# RGB_Display.net
KiCad netlist of a schematic drawn in Altium Designer
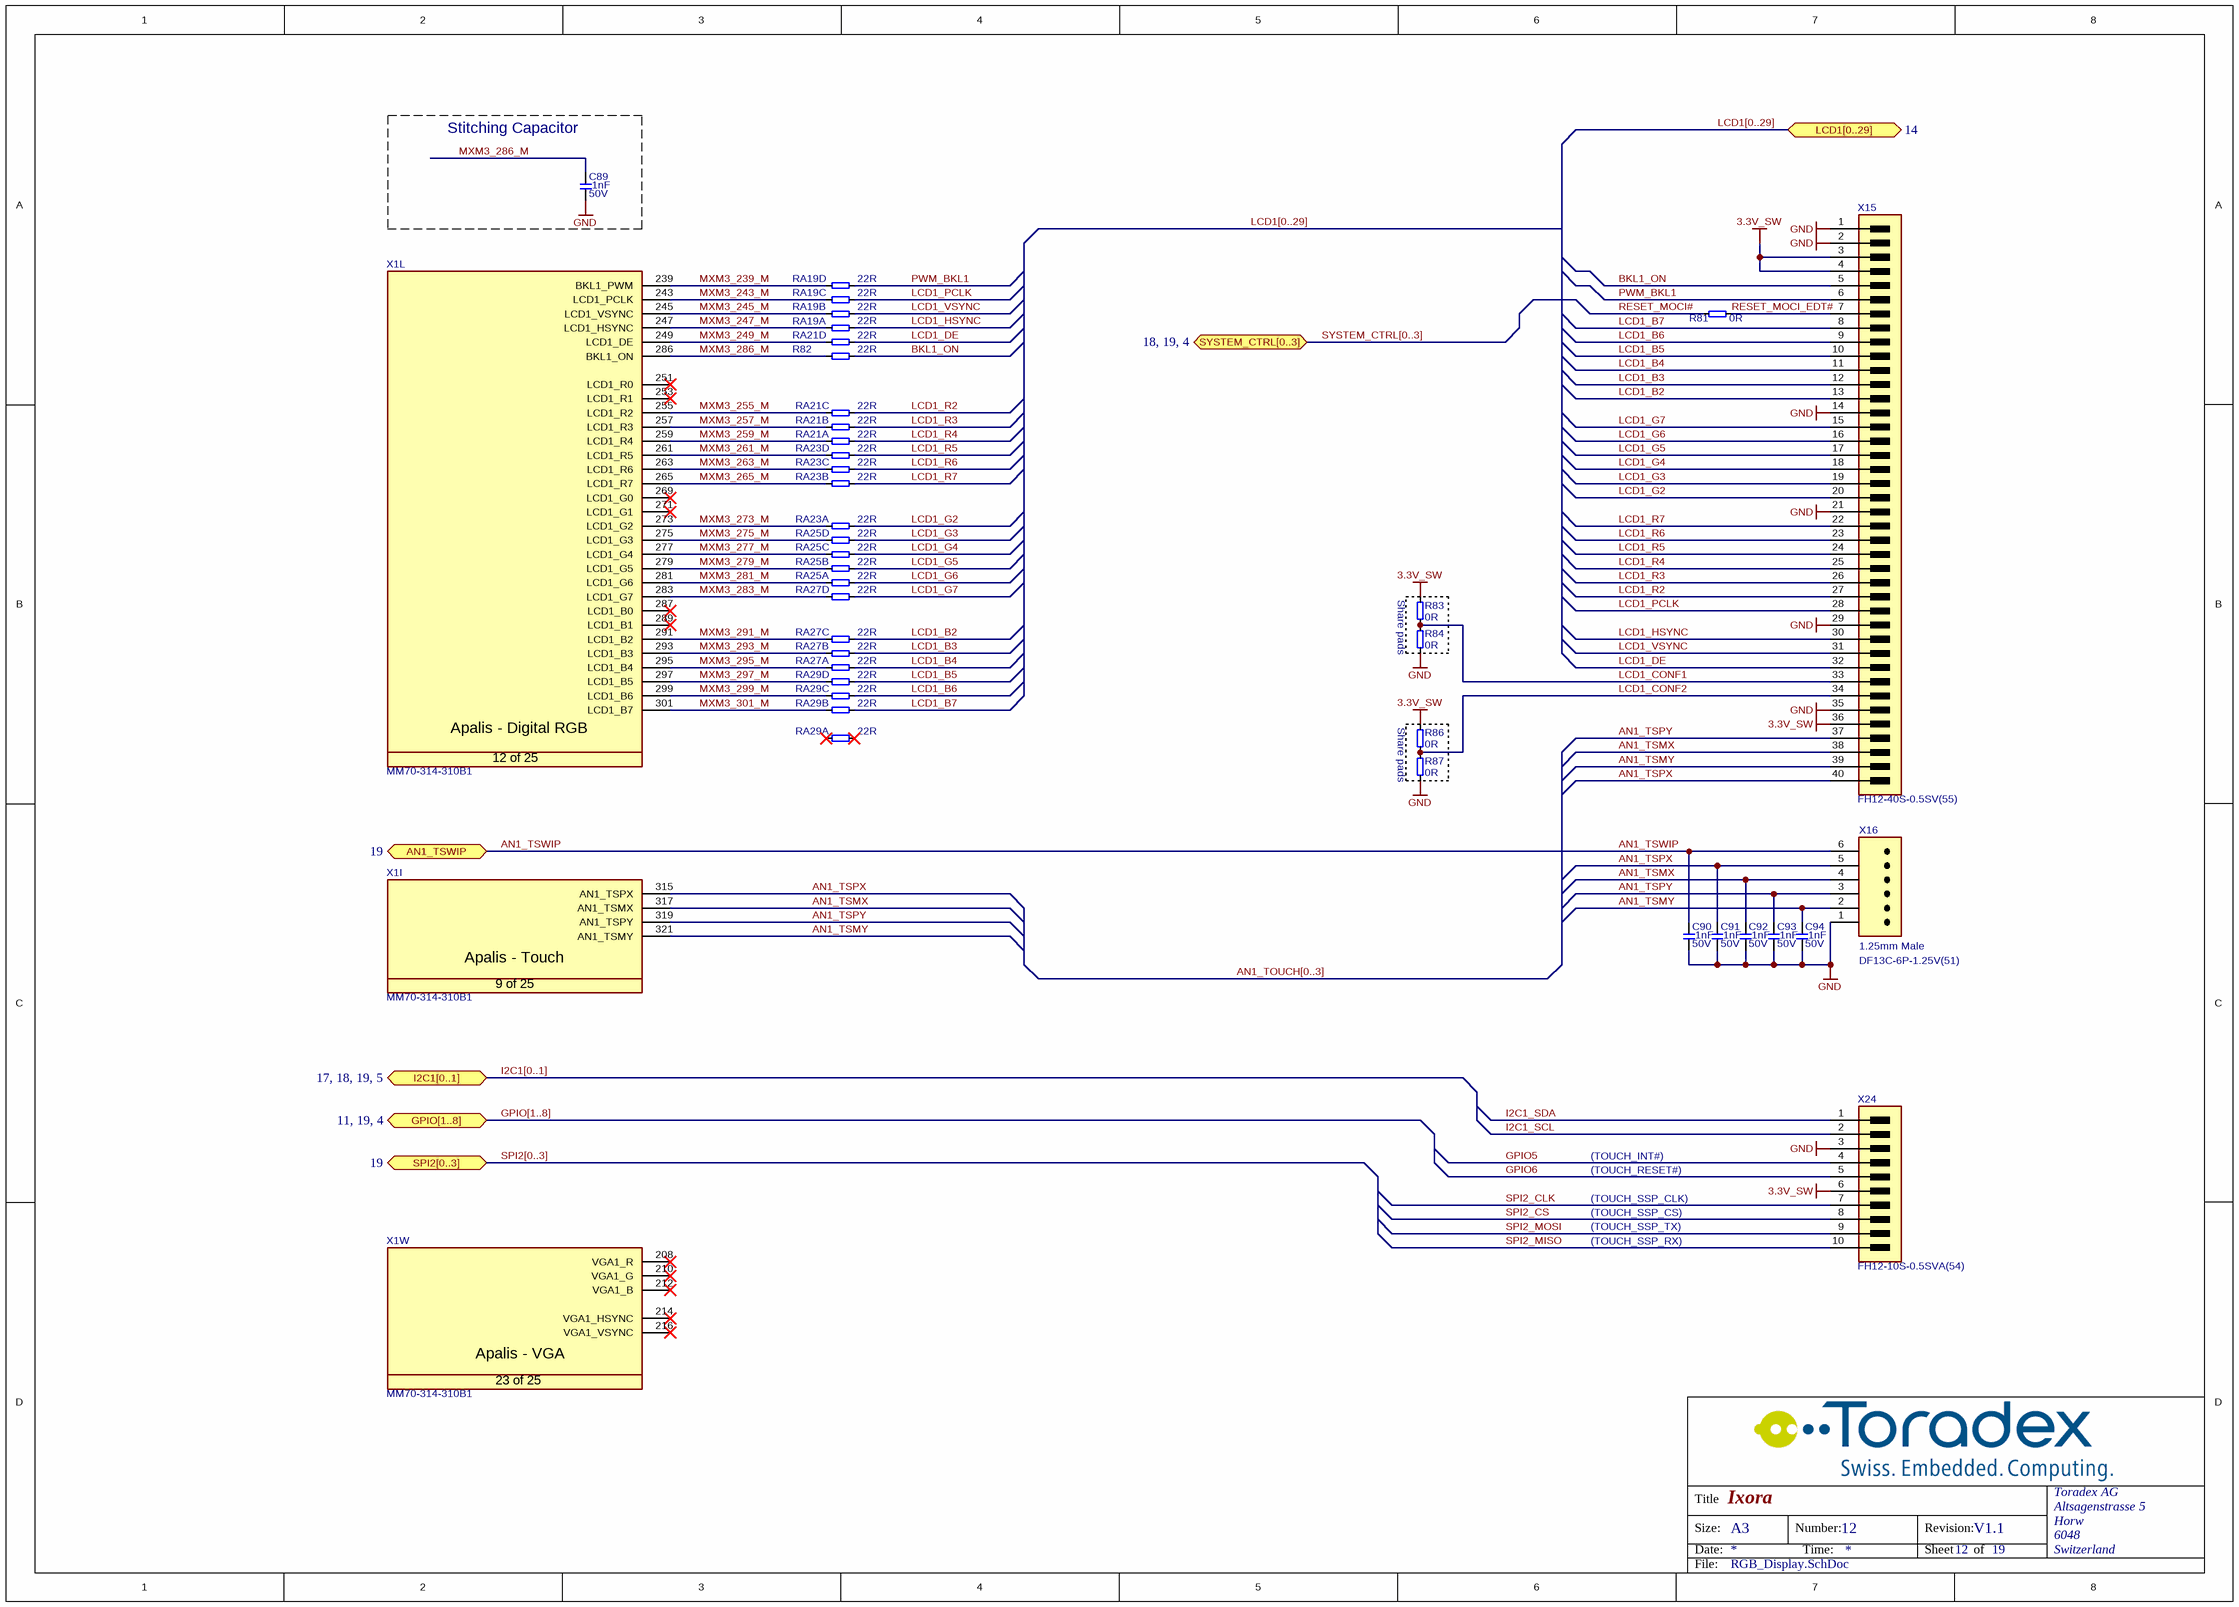
[diagram p0: RGB_Display.SchDoc]

(export (version "E")
  (design (tool "Eeschema 10.0.6"))
  (components
    (comp (ref "C89")
      (value "1nF")
      (footprint "CAPC1005X60N")
      (description "Capacitor Ceramic X7R 1nF 50V 10% 0402")
      (fields (field (name "TOLERANCE") "10%") (field (name "RATING") "50V"))
      (libsource (lib "Ixora") (part "C-X7R-1nF-50V-10%-0402"))
    )
    (comp (ref "C90")
      (value "1nF")
      (footprint "CAPC1005X60N")
      (description "Capacitor Ceramic X7R 1nF 50V 10% 0402")
      (fields (field (name "TOLERANCE") "10%") (field (name "RATING") "50V"))
      (libsource (lib "Ixora") (part "C-X7R-1nF-50V-10%-0402"))
    )
    (comp (ref "C91")
      (value "1nF")
      (footprint "CAPC1005X60N")
      (description "Capacitor Ceramic X7R 1nF 50V 10% 0402")
      (fields (field (name "TOLERANCE") "10%") (field (name "RATING") "50V"))
      (libsource (lib "Ixora") (part "C-X7R-1nF-50V-10%-0402"))
    )
    (comp (ref "C92")
      (value "1nF")
      (footprint "CAPC1005X60N")
      (description "Capacitor Ceramic X7R 1nF 50V 10% 0402")
      (fields (field (name "TOLERANCE") "10%") (field (name "RATING") "50V"))
      (libsource (lib "Ixora") (part "C-X7R-1nF-50V-10%-0402"))
    )
    (comp (ref "C93")
      (value "1nF")
      (footprint "CAPC1005X60N")
      (description "Capacitor Ceramic X7R 1nF 50V 10% 0402")
      (fields (field (name "TOLERANCE") "10%") (field (name "RATING") "50V"))
      (libsource (lib "Ixora") (part "C-X7R-1nF-50V-10%-0402"))
    )
    (comp (ref "C94")
      (value "1nF")
      (footprint "CAPC1005X60N")
      (description "Capacitor Ceramic X7R 1nF 50V 10% 0402")
      (fields (field (name "TOLERANCE") "10%") (field (name "RATING") "50V"))
      (libsource (lib "Ixora") (part "C-X7R-1nF-50V-10%-0402"))
    )
    (comp (ref "R81")
      (value "0R")
      (footprint "RESC1005X40N")
      (description "Resistor 0 ohm 63mW 1% 0402")
      (fields (field (name "TOLERANCE") "1%"))
      (libsource (lib "Ixora") (part "R-0R-63mW-1%-0402"))
    )
    (comp (ref "R82")
      (value "22R")
      (footprint "RESC1005X40N")
      (description "Resistor 22 ohm 63mW 5% 0402")
      (fields (field (name "TOLERANCE") "5%"))
      (libsource (lib "Ixora") (part "R-22R-63mW-5%-0402"))
    )
    (comp (ref "R83")
      (value "0R")
      (footprint "T_RESC0603X30N")
      (description "Resistor 0 ohm 63mW 1% 0603")
      (fields (field (name "TOLERANCE") "1%"))
      (libsource (lib "Ixora") (part "R-0R-63mW-1%-0603"))
    )
    (comp (ref "R84")
      (value "0R")
      (footprint "T_RESC0603X30N")
      (description "Resistor 0 ohm 63mW 1% 0603")
      (fields (field (name "TOLERANCE") "1%"))
      (libsource (lib "Ixora") (part "R-0R-63mW-1%-0603"))
    )
    (comp (ref "R86")
      (value "0R")
      (footprint "T_RESC0603X30N")
      (description "Resistor 0 ohm 63mW 1% 0603")
      (fields (field (name "TOLERANCE") "1%"))
      (libsource (lib "Ixora") (part "R-0R-63mW-1%-0603"))
    )
    (comp (ref "R87")
      (value "0R")
      (footprint "T_RESC0603X30N")
      (description "Resistor 0 ohm 63mW 1% 0603")
      (fields (field (name "TOLERANCE") "1%"))
      (libsource (lib "Ixora") (part "R-0R-63mW-1%-0603"))
    )
    (comp (ref "RA19")
      (value "22R")
      (footprint "T_Resistor_Array_X4")
      (description "Resistor Array 22 R 63mW 5% 1206")
      (fields (field (name "TOLERANCE") "5%"))
      (libsource (lib "Ixora") (part "RA-22R-63mW-5%-1206-div"))
    )
    (comp (ref "RA21")
      (value "22R")
      (footprint "T_Resistor_Array_X4")
      (description "Resistor Array 22 R 63mW 5% 1206")
      (fields (field (name "TOLERANCE") "5%"))
      (libsource (lib "Ixora") (part "RA-22R-63mW-5%-1206-div"))
    )
    (comp (ref "RA23")
      (value "22R")
      (footprint "T_Resistor_Array_X4")
      (description "Resistor Array 22 R 63mW 5% 1206")
      (fields (field (name "TOLERANCE") "5%"))
      (libsource (lib "Ixora") (part "RA-22R-63mW-5%-1206-div"))
    )
    (comp (ref "RA25")
      (value "22R")
      (footprint "T_Resistor_Array_X4")
      (description "Resistor Array 22 R 63mW 5% 1206")
      (fields (field (name "TOLERANCE") "5%"))
      (libsource (lib "Ixora") (part "RA-22R-63mW-5%-1206-div"))
    )
    (comp (ref "RA27")
      (value "22R")
      (footprint "T_Resistor_Array_X4")
      (description "Resistor Array 22 R 63mW 5% 1206")
      (fields (field (name "TOLERANCE") "5%"))
      (libsource (lib "Ixora") (part "RA-22R-63mW-5%-1206-div"))
    )
    (comp (ref "RA29")
      (value "22R")
      (footprint "T_Resistor_Array_X4")
      (description "Resistor Array 22 R 63mW 5% 1206")
      (fields (field (name "TOLERANCE") "5%"))
      (libsource (lib "Ixora") (part "RA-22R-63mW-5%-1206-div"))
    )
    (comp (ref "X1")
      (value "CON-JAE-MM70-314-310B1-314-0.5mm")
      (footprint "T_JAE_MM70-314-310B1")
      (description "MXM3 Connector")
      (fields (field (name "MANUFACTURER PART NO.") "MM70-314-310B1"))
      (libsource (lib "Ixora") (part "CON-JAE-MM70-314-310B1-314-0.5mm"))
    )
    (comp (ref "X15")
      (value "FH12-40S-0.5SV(55)")
      (footprint "T_Hirose_FH12-40S-0.5SV(55)")
      (description "0.50mm Pitch FFC/FPC Vertical RGB connector")
      (fields (field (name "MANUFACTURER PART NO.") "FH12-40S-0.5SV(55)"))
      (libsource (lib "Ixora") (part "CON-Hirose-FH12-40S-0.5SV(55)-0.5mm"))
    )
    (comp (ref "X16")
      (value "DF13C-6P-1.25V(51)")
      (footprint "T_HIROSE_DF13C-6P-1.25V(51)")
      (description "Touch Connector")
      (fields (field (name "MANUFACTURER PART NO.") "DF13C-6P-1.25V(51)"))
      (libsource (lib "Ixora") (part "CON-Hirose-DF13C-6P-1.25V(51)-1x6-1.25mm"))
    )
    (comp (ref "X24")
      (value "FH12-10S-0.5SVA(54)")
      (footprint "T_Hirose_FH12-10S-0.5SVA(54)")
      (description "FFC/FPC, 1 Sided Contact, 0.50mm Pitch, 10 pins")
      (fields (field (name "MANUFACTURER PART NO.") "FH12-10S-0.5SVA(54)"))
      (libsource (lib "Ixora") (part "CON-Hirose-FH12-10S-0.5SVA(54)-0.5mm"))
    )
  )
  (nets
    (net (code "52") (name "/AN1_TSMX") (class "Default")
      (node (ref "C92") (pin "2") (pinfunction "2_2") (pintype "passive"))
      (node (ref "X1") (pin "317") (pinfunction "AN1_TSMX_317") (pintype "passive"))
      (node (ref "X15") (pin "38") (pinfunction "XR_38") (pintype "passive"))
      (node (ref "X16") (pin "4") (pinfunction "TSMX_4") (pintype "passive"))
    )
    (net (code "53") (name "/AN1_TSMY") (class "Default")
      (node (ref "C94") (pin "2") (pinfunction "2_2") (pintype "passive"))
      (node (ref "X1") (pin "321") (pinfunction "AN1_TSMY_321") (pintype "passive"))
      (node (ref "X15") (pin "39") (pinfunction "YD_39") (pintype "passive"))
      (node (ref "X16") (pin "2") (pinfunction "TSMY_2") (pintype "passive"))
    )
    (net (code "54") (name "/AN1_TSPX") (class "Default")
      (node (ref "C91") (pin "2") (pinfunction "2_2") (pintype "passive"))
      (node (ref "X1") (pin "315") (pinfunction "AN1_TSPX_315") (pintype "passive"))
      (node (ref "X15") (pin "40") (pinfunction "XL_40") (pintype "passive"))
      (node (ref "X16") (pin "5") (pinfunction "TSPX_5") (pintype "passive"))
    )
    (net (code "55") (name "/AN1_TSPY") (class "Default")
      (node (ref "C93") (pin "2") (pinfunction "2_2") (pintype "passive"))
      (node (ref "X1") (pin "319") (pinfunction "AN1_TSPY_319") (pintype "passive"))
      (node (ref "X15") (pin "37") (pinfunction "YU_37") (pintype "passive"))
      (node (ref "X16") (pin "3") (pinfunction "TSPY_3") (pintype "passive"))
    )
    (net (code "56") (name "/AN1_TSWIP") (class "Default")
      (node (ref "C90") (pin "2") (pinfunction "2_2") (pintype "passive"))
      (node (ref "X16") (pin "6") (pinfunction "WIPER_6") (pintype "passive"))
    )
    (net (code "57") (name "/BKL1_ON") (class "Default")
      (node (ref "R82") (pin "2") (pinfunction "2_2") (pintype "passive"))
      (node (ref "X15") (pin "5") (pinfunction "PWCTRL_5") (pintype "passive"))
    )
    (net (code "58") (name "/GPIO5") (class "Default")
      (node (ref "X24") (pin "4") (pinfunction "GND_4") (pintype "passive"))
    )
    (net (code "59") (name "/GPIO6") (class "Default")
      (node (ref "X24") (pin "5") (pinfunction "TMDS_DATA0_P_5") (pintype "passive"))
    )
    (net (code "62") (name "/I2C1_SCL") (class "Default")
      (node (ref "X24") (pin "2") (pinfunction "TMDS_CLK_P_2") (pintype "passive"))
    )
    (net (code "63") (name "/I2C1_SDA") (class "Default")
      (node (ref "X24") (pin "1") (pinfunction "GND_1") (pintype "passive"))
    )
    (net (code "65") (name "/LCD1_B2") (class "Default")
      (node (ref "RA27") (pin "7") (pinfunction "7_7") (pintype "passive"))
      (node (ref "X15") (pin "13") (pinfunction "B0_13") (pintype "passive"))
    )
    (net (code "66") (name "/LCD1_B3") (class "Default")
      (node (ref "RA27") (pin "6") (pinfunction "6_6") (pintype "passive"))
      (node (ref "X15") (pin "12") (pinfunction "B1_12") (pintype "passive"))
    )
    (net (code "67") (name "/LCD1_B4") (class "Default")
      (node (ref "RA27") (pin "5") (pinfunction "5_5") (pintype "passive"))
      (node (ref "X15") (pin "11") (pinfunction "B2_11") (pintype "passive"))
    )
    (net (code "68") (name "/LCD1_B5") (class "Default")
      (node (ref "RA29") (pin "8") (pinfunction "8_8") (pintype "passive"))
      (node (ref "X15") (pin "10") (pinfunction "B3_10") (pintype "passive"))
    )
    (net (code "69") (name "/LCD1_B6") (class "Default")
      (node (ref "RA29") (pin "7") (pinfunction "7_7") (pintype "passive"))
      (node (ref "X15") (pin "9") (pinfunction "B4_9") (pintype "passive"))
    )
    (net (code "70") (name "/LCD1_B7") (class "Default")
      (node (ref "RA29") (pin "6") (pinfunction "6_6") (pintype "passive"))
      (node (ref "X15") (pin "8") (pinfunction "B5_8") (pintype "passive"))
    )
    (net (code "71") (name "/LCD1_CONF1") (class "Default")
      (node (ref "R83") (pin "2") (pinfunction "2_2") (pintype "passive"))
      (node (ref "R84") (pin "1") (pinfunction "1_1") (pintype "passive"))
      (node (ref "X15") (pin "33") (pinfunction "NC_33") (pintype "passive"))
    )
    (net (code "72") (name "/LCD1_CONF2") (class "Default")
      (node (ref "R86") (pin "2") (pinfunction "2_2") (pintype "passive"))
      (node (ref "R87") (pin "2") (pinfunction "2_2") (pintype "passive"))
      (node (ref "X15") (pin "34") (pinfunction "SHUT_34") (pintype "passive"))
    )
    (net (code "73") (name "/LCD1_DE") (class "Default")
      (node (ref "RA21") (pin "8") (pinfunction "8_8") (pintype "passive"))
      (node (ref "X15") (pin "32") (pinfunction "ENB_32") (pintype "passive"))
    )
    (net (code "74") (name "/LCD1_G2") (class "Default")
      (node (ref "RA23") (pin "5") (pinfunction "5_5") (pintype "passive"))
      (node (ref "X15") (pin "20") (pinfunction "G0_20") (pintype "passive"))
    )
    (net (code "75") (name "/LCD1_G3") (class "Default")
      (node (ref "RA25") (pin "8") (pinfunction "8_8") (pintype "passive"))
      (node (ref "X15") (pin "19") (pinfunction "G1_19") (pintype "passive"))
    )
    (net (code "76") (name "/LCD1_G4") (class "Default")
      (node (ref "RA25") (pin "7") (pinfunction "7_7") (pintype "passive"))
      (node (ref "X15") (pin "18") (pinfunction "G2_18") (pintype "passive"))
    )
    (net (code "77") (name "/LCD1_G5") (class "Default")
      (node (ref "RA25") (pin "6") (pinfunction "6_6") (pintype "passive"))
      (node (ref "X15") (pin "17") (pinfunction "G3_17") (pintype "passive"))
    )
    (net (code "78") (name "/LCD1_G6") (class "Default")
      (node (ref "RA25") (pin "5") (pinfunction "5_5") (pintype "passive"))
      (node (ref "X15") (pin "16") (pinfunction "G4_16") (pintype "passive"))
    )
    (net (code "79") (name "/LCD1_G7") (class "Default")
      (node (ref "RA27") (pin "8") (pinfunction "8_8") (pintype "passive"))
      (node (ref "X15") (pin "15") (pinfunction "G5_15") (pintype "passive"))
    )
    (net (code "80") (name "/LCD1_HSYNC") (class "Default")
      (node (ref "RA19") (pin "5") (pinfunction "5_5") (pintype "passive"))
      (node (ref "X15") (pin "30") (pinfunction "HSYNC_30") (pintype "passive"))
    )
    (net (code "81") (name "/LCD1_PCLK") (class "Default")
      (node (ref "RA19") (pin "7") (pinfunction "7_7") (pintype "passive"))
      (node (ref "X15") (pin "28") (pinfunction "DCLK_28") (pintype "passive"))
    )
    (net (code "82") (name "/LCD1_R2") (class "Default")
      (node (ref "RA21") (pin "7") (pinfunction "7_7") (pintype "passive"))
      (node (ref "X15") (pin "27") (pinfunction "R0_27") (pintype "passive"))
    )
    (net (code "83") (name "/LCD1_R3") (class "Default")
      (node (ref "RA21") (pin "6") (pinfunction "6_6") (pintype "passive"))
      (node (ref "X15") (pin "26") (pinfunction "R1_26") (pintype "passive"))
    )
    (net (code "84") (name "/LCD1_R4") (class "Default")
      (node (ref "RA21") (pin "5") (pinfunction "5_5") (pintype "passive"))
      (node (ref "X15") (pin "25") (pinfunction "R2_25") (pintype "passive"))
    )
    (net (code "85") (name "/LCD1_R5") (class "Default")
      (node (ref "RA23") (pin "8") (pinfunction "8_8") (pintype "passive"))
      (node (ref "X15") (pin "24") (pinfunction "R3_24") (pintype "passive"))
    )
    (net (code "86") (name "/LCD1_R6") (class "Default")
      (node (ref "RA23") (pin "7") (pinfunction "7_7") (pintype "passive"))
      (node (ref "X15") (pin "23") (pinfunction "R4_23") (pintype "passive"))
    )
    (net (code "87") (name "/LCD1_R7") (class "Default")
      (node (ref "RA23") (pin "6") (pinfunction "6_6") (pintype "passive"))
      (node (ref "X15") (pin "22") (pinfunction "R5_22") (pintype "passive"))
    )
    (net (code "88") (name "/LCD1_VSYNC") (class "Default")
      (node (ref "RA19") (pin "6") (pinfunction "6_6") (pintype "passive"))
      (node (ref "X15") (pin "31") (pinfunction "VSYNC_31") (pintype "passive"))
    )
    (net (code "89") (name "/MXM3_239_M") (class "Default")
      (node (ref "RA19") (pin "4") (pinfunction "4_4") (pintype "passive"))
      (node (ref "X1") (pin "239") (pinfunction "BKL1_PWM_239") (pintype "passive"))
    )
    (net (code "90") (name "/MXM3_243_M") (class "Default")
      (node (ref "RA19") (pin "3") (pinfunction "3_3") (pintype "passive"))
      (node (ref "X1") (pin "243") (pinfunction "LCD1_PCLK_243") (pintype "passive"))
    )
    (net (code "91") (name "/MXM3_245_M") (class "Default")
      (node (ref "RA19") (pin "2") (pinfunction "2_2") (pintype "passive"))
      (node (ref "X1") (pin "245") (pinfunction "LCD1_VSYNC_245") (pintype "passive"))
    )
    (net (code "92") (name "/MXM3_247_M") (class "Default")
      (node (ref "RA19") (pin "1") (pinfunction "1_1") (pintype "passive"))
      (node (ref "X1") (pin "247") (pinfunction "LCD1_HSYNC_247") (pintype "passive"))
    )
    (net (code "93") (name "/MXM3_249_M") (class "Default")
      (node (ref "RA21") (pin "4") (pinfunction "4_4") (pintype "passive"))
      (node (ref "X1") (pin "249") (pinfunction "LCD1_DE_249") (pintype "passive"))
    )
    (net (code "94") (name "/MXM3_255_M") (class "Default")
      (node (ref "RA21") (pin "3") (pinfunction "3_3") (pintype "passive"))
      (node (ref "X1") (pin "255") (pinfunction "LCD1_R2_255") (pintype "passive"))
    )
    (net (code "95") (name "/MXM3_257_M") (class "Default")
      (node (ref "RA21") (pin "2") (pinfunction "2_2") (pintype "passive"))
      (node (ref "X1") (pin "257") (pinfunction "LCD1_R3_257") (pintype "passive"))
    )
    (net (code "96") (name "/MXM3_259_M") (class "Default")
      (node (ref "RA21") (pin "1") (pinfunction "1_1") (pintype "passive"))
      (node (ref "X1") (pin "259") (pinfunction "LCD1_R4_259") (pintype "passive"))
    )
    (net (code "97") (name "/MXM3_261_M") (class "Default")
      (node (ref "RA23") (pin "4") (pinfunction "4_4") (pintype "passive"))
      (node (ref "X1") (pin "261") (pinfunction "LCD1_R5_261") (pintype "passive"))
    )
    (net (code "98") (name "/MXM3_263_M") (class "Default")
      (node (ref "RA23") (pin "3") (pinfunction "3_3") (pintype "passive"))
      (node (ref "X1") (pin "263") (pinfunction "LCD1_R6_263") (pintype "passive"))
    )
    (net (code "99") (name "/MXM3_265_M") (class "Default")
      (node (ref "RA23") (pin "2") (pinfunction "2_2") (pintype "passive"))
      (node (ref "X1") (pin "265") (pinfunction "LCD1_R7_265") (pintype "passive"))
    )
    (net (code "100") (name "/MXM3_273_M") (class "Default")
      (node (ref "RA23") (pin "1") (pinfunction "1_1") (pintype "passive"))
      (node (ref "X1") (pin "273") (pinfunction "LCD1_G2_273") (pintype "passive"))
    )
    (net (code "101") (name "/MXM3_275_M") (class "Default")
      (node (ref "RA25") (pin "4") (pinfunction "4_4") (pintype "passive"))
      (node (ref "X1") (pin "275") (pinfunction "LCD1_G3_275") (pintype "passive"))
    )
    (net (code "102") (name "/MXM3_277_M") (class "Default")
      (node (ref "RA25") (pin "3") (pinfunction "3_3") (pintype "passive"))
      (node (ref "X1") (pin "277") (pinfunction "LCD1_G4_277") (pintype "passive"))
    )
    (net (code "103") (name "/MXM3_279_M") (class "Default")
      (node (ref "RA25") (pin "2") (pinfunction "2_2") (pintype "passive"))
      (node (ref "X1") (pin "279") (pinfunction "LCD1_G5_279") (pintype "passive"))
    )
    (net (code "104") (name "/MXM3_281_M") (class "Default")
      (node (ref "RA25") (pin "1") (pinfunction "1_1") (pintype "passive"))
      (node (ref "X1") (pin "281") (pinfunction "LCD1_G6_281") (pintype "passive"))
    )
    (net (code "105") (name "/MXM3_283_M") (class "Default")
      (node (ref "RA27") (pin "4") (pinfunction "4_4") (pintype "passive"))
      (node (ref "X1") (pin "283") (pinfunction "LCD1_G7_283") (pintype "passive"))
    )
    (net (code "106") (name "/MXM3_286_M") (class "Default")
      (node (ref "C89") (pin "2") (pinfunction "2_2") (pintype "passive"))
      (node (ref "R82") (pin "1") (pinfunction "1_1") (pintype "passive"))
      (node (ref "X1") (pin "286") (pinfunction "BKL1_ON_286") (pintype "passive"))
    )
    (net (code "107") (name "/MXM3_291_M") (class "Default")
      (node (ref "RA27") (pin "3") (pinfunction "3_3") (pintype "passive"))
      (node (ref "X1") (pin "291") (pinfunction "LCD1_B2_291") (pintype "passive"))
    )
    (net (code "108") (name "/MXM3_293_M") (class "Default")
      (node (ref "RA27") (pin "2") (pinfunction "2_2") (pintype "passive"))
      (node (ref "X1") (pin "293") (pinfunction "LCD1_B3_293") (pintype "passive"))
    )
    (net (code "109") (name "/MXM3_295_M") (class "Default")
      (node (ref "RA27") (pin "1") (pinfunction "1_1") (pintype "passive"))
      (node (ref "X1") (pin "295") (pinfunction "LCD1_B4_295") (pintype "passive"))
    )
    (net (code "110") (name "/MXM3_297_M") (class "Default")
      (node (ref "RA29") (pin "4") (pinfunction "4_4") (pintype "passive"))
      (node (ref "X1") (pin "297") (pinfunction "LCD1_B5_297") (pintype "passive"))
    )
    (net (code "111") (name "/MXM3_299_M") (class "Default")
      (node (ref "RA29") (pin "3") (pinfunction "3_3") (pintype "passive"))
      (node (ref "X1") (pin "299") (pinfunction "LCD1_B6_299") (pintype "passive"))
    )
    (net (code "112") (name "/MXM3_301_M") (class "Default")
      (node (ref "RA29") (pin "2") (pinfunction "2_2") (pintype "passive"))
      (node (ref "X1") (pin "301") (pinfunction "LCD1_B7_301") (pintype "passive"))
    )
    (net (code "113") (name "/PWM_BKL1") (class "Default")
      (node (ref "RA19") (pin "8") (pinfunction "8_8") (pintype "passive"))
      (node (ref "X15") (pin "6") (pinfunction "LEDCTRL_6") (pintype "passive"))
    )
    (net (code "114") (name "/RESET_MOCI#") (class "Default")
      (node (ref "R81") (pin "1") (pinfunction "1_1") (pintype "passive"))
    )
    (net (code "115") (name "/RESET_MOCI_EDT#") (class "Default")
      (node (ref "R81") (pin "2") (pinfunction "2_2") (pintype "passive"))
      (node (ref "X15") (pin "7") (pinfunction "RESET#_7") (pintype "passive"))
    )
    (net (code "117") (name "/SPI2_CLK") (class "Default")
      (node (ref "X24") (pin "7") (pinfunction "GND_7") (pintype "passive"))
    )
    (net (code "118") (name "/SPI2_CS") (class "Default")
      (node (ref "X24") (pin "8") (pinfunction "TMDS_DATA1_P_8") (pintype "passive"))
    )
    (net (code "119") (name "/SPI2_MISO") (class "Default")
      (node (ref "X24") (pin "10") (pinfunction "GND_10") (pintype "passive"))
    )
    (net (code "120") (name "/SPI2_MOSI") (class "Default")
      (node (ref "X24") (pin "9") (pinfunction "TMDS_DATA1_N_9") (pintype "passive"))
    )
    (net (code "122") (name "3.3V_SW") (class "Default")
      (node (ref "R83") (pin "1") (pinfunction "1_1") (pintype "passive"))
      (node (ref "R86") (pin "1") (pinfunction "1_1") (pintype "passive"))
      (node (ref "X15") (pin "3") (pinfunction "VCC_3") (pintype "power_in"))
      (node (ref "X15") (pin "36") (pinfunction "VDD_36") (pintype "passive"))
      (node (ref "X15") (pin "4") (pinfunction "VCC_4") (pintype "power_in"))
      (node (ref "X24") (pin "6") (pinfunction "TMDS_DATA0_N_6") (pintype "passive"))
    )
    (net (code "123") (name "GND") (class "Default")
      (node (ref "C89") (pin "1") (pinfunction "1_1") (pintype "passive"))
      (node (ref "C90") (pin "1") (pinfunction "1_1") (pintype "passive"))
      (node (ref "C91") (pin "1") (pinfunction "1_1") (pintype "passive"))
      (node (ref "C92") (pin "1") (pinfunction "1_1") (pintype "passive"))
      (node (ref "C93") (pin "1") (pinfunction "1_1") (pintype "passive"))
      (node (ref "C94") (pin "1") (pinfunction "1_1") (pintype "passive"))
      (node (ref "R84") (pin "2") (pinfunction "2_2") (pintype "passive"))
      (node (ref "R87") (pin "1") (pinfunction "1_1") (pintype "passive"))
      (node (ref "X15") (pin "1") (pinfunction "VSS_1") (pintype "power_in"))
      (node (ref "X15") (pin "14") (pinfunction "VSS_14") (pintype "passive"))
      (node (ref "X15") (pin "2") (pinfunction "VSS_2") (pintype "power_in"))
      (node (ref "X15") (pin "21") (pinfunction "VSS_21") (pintype "passive"))
      (node (ref "X15") (pin "29") (pinfunction "VSS_29") (pintype "passive"))
      (node (ref "X15") (pin "35") (pinfunction "VSS_35") (pintype "passive"))
      (node (ref "X16") (pin "1") (pinfunction "GND_1") (pintype "passive"))
      (node (ref "X24") (pin "3") (pinfunction "TMDS_CLK_N_3") (pintype "passive"))
    )
    (net (code "124") (name "unconnected-(RA29-Pad1)") (class "Default")
      (node (ref "RA29") (pin "1") (pinfunction "1_1") (pintype "passive+no_connect"))
    )
    (net (code "125") (name "unconnected-(RA29-Pad5)") (class "Default")
      (node (ref "RA29") (pin "5") (pinfunction "5_5") (pintype "passive+no_connect"))
    )
    (net (code "126") (name "unconnected-(X1L-LCD1_B0-Pad287)") (class "Default")
      (node (ref "X1") (pin "287") (pinfunction "LCD1_B0_287") (pintype "passive+no_connect"))
    )
    (net (code "127") (name "unconnected-(X1L-LCD1_B1-Pad289)") (class "Default")
      (node (ref "X1") (pin "289") (pinfunction "LCD1_B1_289") (pintype "passive+no_connect"))
    )
    (net (code "128") (name "unconnected-(X1L-LCD1_G0-Pad269)") (class "Default")
      (node (ref "X1") (pin "269") (pinfunction "LCD1_G0_269") (pintype "passive+no_connect"))
    )
    (net (code "129") (name "unconnected-(X1L-LCD1_G1-Pad271)") (class "Default")
      (node (ref "X1") (pin "271") (pinfunction "LCD1_G1_271") (pintype "passive+no_connect"))
    )
    (net (code "130") (name "unconnected-(X1L-LCD1_R0-Pad251)") (class "Default")
      (node (ref "X1") (pin "251") (pinfunction "LCD1_R0_251") (pintype "passive+no_connect"))
    )
    (net (code "131") (name "unconnected-(X1L-LCD1_R1-Pad253)") (class "Default")
      (node (ref "X1") (pin "253") (pinfunction "LCD1_R1_253") (pintype "passive+no_connect"))
    )
    (net (code "132") (name "unconnected-(X1W-VGA1_B-Pad212)") (class "Default")
      (node (ref "X1") (pin "212") (pinfunction "VGA1_B_212") (pintype "passive+no_connect"))
    )
    (net (code "133") (name "unconnected-(X1W-VGA1_G-Pad210)") (class "Default")
      (node (ref "X1") (pin "210") (pinfunction "VGA1_G_210") (pintype "passive+no_connect"))
    )
    (net (code "134") (name "unconnected-(X1W-VGA1_HSYNC-Pad214)") (class "Default")
      (node (ref "X1") (pin "214") (pinfunction "VGA1_HSYNC_214") (pintype "passive+no_connect"))
    )
    (net (code "135") (name "unconnected-(X1W-VGA1_R-Pad208)") (class "Default")
      (node (ref "X1") (pin "208") (pinfunction "VGA1_R_208") (pintype "passive+no_connect"))
    )
    (net (code "136") (name "unconnected-(X1W-VGA1_VSYNC-Pad216)") (class "Default")
      (node (ref "X1") (pin "216") (pinfunction "VGA1_VSYNC_216") (pintype "passive+no_connect"))
    )
  )
)
